# MCU.net
KiCad netlist of a schematic drawn in Altium Designer
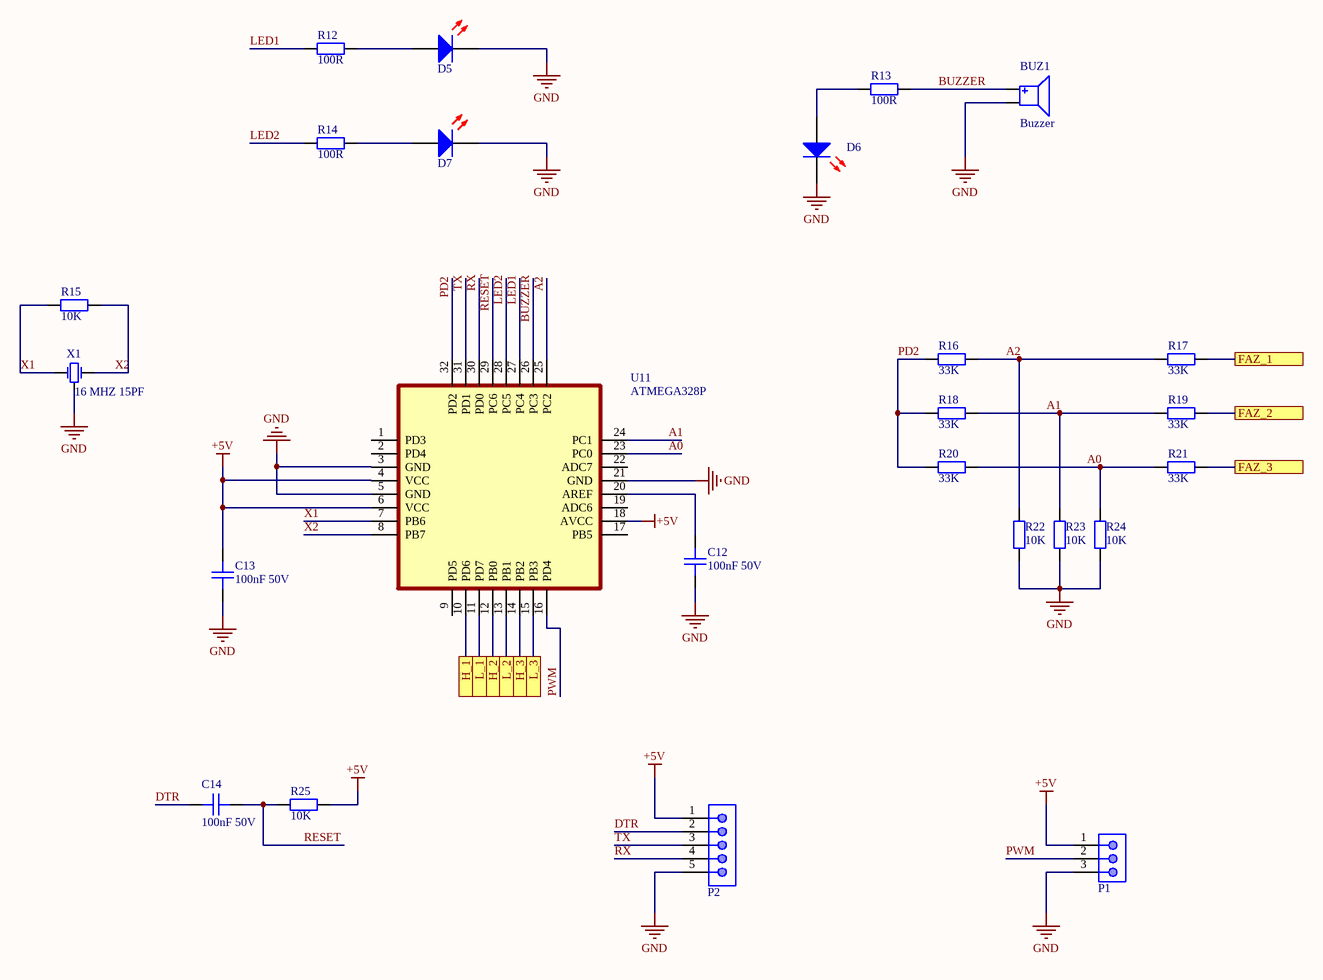
[diagram p0: MCU.SchDoc]

(export (version "E")
  (design (tool "Eeschema 10.0.6"))
  (components
    (comp (ref "BUZ1")
      (value "BUZZER MAGN 3.6V 7.5X7.5MM SMD")
      (footprint "BUZ: CMT-7525")
      (fields (field (name "DEGER") "Buzzer"))
      (libsource (lib "PROJE") (part "Buzzer(CMT-7525-80-SMT-TR)"))
    )
    (comp (ref "C12")
      (value "CAP CER 0.1UF 50V X7R 0805")
      (footprint "CAP 0805/2012")
      (description "0.1µF ±10% 50V Ceramic Capacitor X7R 0805 (2012 Metric)")
      (fields (field (name "DEGER") "100nF 50V"))
      (libsource (lib "PROJE") (part "100nF 50V 0805"))
    )
    (comp (ref "C13")
      (value "CAP CER 0.1UF 50V X7R 0805")
      (footprint "CAP 0805/2012")
      (description "0.1µF ±10% 50V Ceramic Capacitor X7R 0805 (2012 Metric)")
      (fields (field (name "DEGER") "100nF 50V"))
      (libsource (lib "PROJE") (part "100nF 50V 0805"))
    )
    (comp (ref "C14")
      (value "CAP CER 0.1UF 50V X7R 0805")
      (footprint "CAP 0805/2012")
      (description "0.1µF ±10% 50V Ceramic Capacitor X7R 0805 (2012 Metric)")
      (fields (field (name "DEGER") "100nF 50V"))
      (libsource (lib "PROJE") (part "100nF 50V 0805"))
    )
    (comp (ref "D5")
      (value "Red 645nm LED Indication - Discrete 1.8V 0805")
      (footprint "SMD: LED 0805/2012 RED")
      (description "LED RED DIFFUSED 0805 SMD")
      (libsource (lib "PROJE") (part "LED_Kırmızı"))
    )
    (comp (ref "D6")
      (value "Red 645nm LED Indication - Discrete 1.8V 0805")
      (footprint "SMD: LED 0805/2012 RED")
      (description "LED RED DIFFUSED 0805 SMD")
      (libsource (lib "PROJE") (part "LED_Kırmızı"))
    )
    (comp (ref "D7")
      (value "Red 645nm LED Indication - Discrete 1.8V 0805")
      (footprint "SMD: LED 0805/2012 RED")
      (description "LED RED DIFFUSED 0805 SMD")
      (libsource (lib "PROJE") (part "LED_Kırmızı"))
    )
    (comp (ref "P1")
      (value "WR-PHD 2.54 mm Angled Socket Header")
      (footprint "PWM_CONN")
      (libsource (lib "PROJE") (part "HDR(1X3)"))
    )
    (comp (ref "P2")
      (value "WR-PHD 2.54 mm Angled Socket Header")
      (footprint "TTL_CONN_5")
      (libsource (lib "PROJE") (part "HDR(1X5)"))
    )
    (comp (ref "R12")
      (value "RES SMD 100 OHM 1% 1/8W 0805")
      (footprint "RES_0805")
      (description "100 Ohms ±1% 0.125W, 1/8W Chip Resistor 0805 (2012 Metric) Moisture Resistant Thick Film")
      (fields (field (name "DEGER") "100R"))
      (libsource (lib "PROJE") (part "100R 0805"))
    )
    (comp (ref "R13")
      (value "RES SMD 100 OHM 1% 1/8W 0805")
      (footprint "RES_0805")
      (description "100 Ohms ±1% 0.125W, 1/8W Chip Resistor 0805 (2012 Metric) Moisture Resistant Thick Film")
      (fields (field (name "DEGER") "100R"))
      (libsource (lib "PROJE") (part "100R 0805"))
    )
    (comp (ref "R14")
      (value "RES SMD 100 OHM 1% 1/8W 0805")
      (footprint "RES_0805")
      (description "100 Ohms ±1% 0.125W, 1/8W Chip Resistor 0805 (2012 Metric) Moisture Resistant Thick Film")
      (fields (field (name "DEGER") "100R"))
      (libsource (lib "PROJE") (part "100R 0805"))
    )
    (comp (ref "R15")
      (value "RES SMD 10K OHM 1% 1/8W 0805")
      (footprint "RES_0805")
      (description "10 kOhms ±1% 0.125W, 1/8W Chip Resistor 0805 (2012 Metric) Moisture Resistant Thick Film")
      (fields (field (name "DEGER") "10K"))
      (libsource (lib "") (part "10K 0805_1"))
    )
    (comp (ref "R16")
      (value "RES SMD 33K OHM 1% 1/8W 0805")
      (footprint "RES_0805")
      (description "33 kOhms ±1% 0.125W, 1/8W Chip Resistor 0805 (2012 Metric) Moisture Resistant Thick Film")
      (fields (field (name "DEGER") "33K"))
      (libsource (lib "PROJE") (part "33K 0805"))
    )
    (comp (ref "R17")
      (value "RES SMD 33K OHM 1% 1/8W 0805")
      (footprint "RES_0805")
      (description "33 kOhms ±1% 0.125W, 1/8W Chip Resistor 0805 (2012 Metric) Moisture Resistant Thick Film")
      (fields (field (name "DEGER") "33K"))
      (libsource (lib "PROJE") (part "33K 0805"))
    )
    (comp (ref "R18")
      (value "RES SMD 33K OHM 1% 1/8W 0805")
      (footprint "RES_0805")
      (description "33 kOhms ±1% 0.125W, 1/8W Chip Resistor 0805 (2012 Metric) Moisture Resistant Thick Film")
      (fields (field (name "DEGER") "33K"))
      (libsource (lib "PROJE") (part "33K 0805"))
    )
    (comp (ref "R19")
      (value "RES SMD 33K OHM 1% 1/8W 0805")
      (footprint "RES_0805")
      (description "33 kOhms ±1% 0.125W, 1/8W Chip Resistor 0805 (2012 Metric) Moisture Resistant Thick Film")
      (fields (field (name "DEGER") "33K"))
      (libsource (lib "PROJE") (part "33K 0805"))
    )
    (comp (ref "R20")
      (value "RES SMD 33K OHM 1% 1/8W 0805")
      (footprint "RES_0805")
      (description "33 kOhms ±1% 0.125W, 1/8W Chip Resistor 0805 (2012 Metric) Moisture Resistant Thick Film")
      (fields (field (name "DEGER") "33K"))
      (libsource (lib "PROJE") (part "33K 0805"))
    )
    (comp (ref "R21")
      (value "RES SMD 33K OHM 1% 1/8W 0805")
      (footprint "RES_0805")
      (description "33 kOhms ±1% 0.125W, 1/8W Chip Resistor 0805 (2012 Metric) Moisture Resistant Thick Film")
      (fields (field (name "DEGER") "33K"))
      (libsource (lib "PROJE") (part "33K 0805"))
    )
    (comp (ref "R22")
      (value "RES SMD 10K OHM 1% 1/8W 0805")
      (footprint "RES_0805")
      (description "10 kOhms ±1% 0.125W, 1/8W Chip Resistor 0805 (2012 Metric) Moisture Resistant Thick Film")
      (fields (field (name "DEGER") "10K"))
      (libsource (lib "PROJE") (part "10K 0805"))
    )
    (comp (ref "R23")
      (value "RES SMD 10K OHM 1% 1/8W 0805")
      (footprint "RES_0805")
      (description "10 kOhms ±1% 0.125W, 1/8W Chip Resistor 0805 (2012 Metric) Moisture Resistant Thick Film")
      (fields (field (name "DEGER") "10K"))
      (libsource (lib "PROJE") (part "10K 0805"))
    )
    (comp (ref "R24")
      (value "RES SMD 10K OHM 1% 1/8W 0805")
      (footprint "RES_0805")
      (description "10 kOhms ±1% 0.125W, 1/8W Chip Resistor 0805 (2012 Metric) Moisture Resistant Thick Film")
      (fields (field (name "DEGER") "10K"))
      (libsource (lib "PROJE") (part "10K 0805"))
    )
    (comp (ref "R25")
      (value "RES SMD 10K OHM 1% 1/8W 0805")
      (footprint "RES_0805")
      (description "10 kOhms ±1% 0.125W, 1/8W Chip Resistor 0805 (2012 Metric) Moisture Resistant Thick Film")
      (fields (field (name "DEGER") "10K"))
      (libsource (lib "") (part "10K 0805_1"))
    )
    (comp (ref "U11")
      (value "IC MCU 8BIT 32KB FLASH 32TQFP")
      (footprint "TQFP32")
      (description "AVR AVR® ATmega Microcontroller IC 8-Bit 20MHz 32KB (16K x 16) FLASH 32-TQFP (7x7)")
      (fields (field (name "DEGER") "ATMEGA328P"))
      (libsource (lib "PROJE") (part "ATMEGA328P"))
    )
    (comp (ref "X1")
      (value "CERAMIC RES 16.0000MHZ 15PF SMD")
      (footprint "CRYSTAL_16MHZ(CTSE16)")
      (description "16MHz Ceramic Resonator Built in Capacitor 15pF ±0.3%  -20°C ~ 80°C Surface Mount")
      (fields (field (name "DEGER") "16 MHZ 15PF"))
      (libsource (lib "PROJE") (part "CRYSTAL 16.0000MHZ(CSTCE16M0V53-R0)"))
    )
  )
  (nets
    (net (code "1") (name "+5V") (class "Default")
      (node (ref "C13") (pin "2") (pinfunction "2_2") (pintype "passive"))
      (node (ref "P1") (pin "1") (pinfunction "1_1") (pintype "passive"))
      (node (ref "P2") (pin "1") (pinfunction "1_1") (pintype "passive"))
      (node (ref "R25") (pin "2") (pinfunction "2_2") (pintype "passive"))
      (node (ref "U11") (pin "18") (pinfunction "AVCC_18") (pintype "passive"))
      (node (ref "U11") (pin "4") (pinfunction "VCC_4") (pintype "passive"))
      (node (ref "U11") (pin "6") (pinfunction "VCC_6") (pintype "passive"))
    )
    (net (code "2") (name "/A0") (class "Default")
      (node (ref "R20") (pin "2") (pinfunction "2_2") (pintype "passive"))
      (node (ref "R21") (pin "1") (pinfunction "1_1") (pintype "passive"))
      (node (ref "R24") (pin "2") (pinfunction "2_2") (pintype "passive"))
      (node (ref "U11") (pin "23") (pinfunction "PC0_23") (pintype "passive"))
    )
    (net (code "3") (name "/A1") (class "Default")
      (node (ref "R18") (pin "2") (pinfunction "2_2") (pintype "passive"))
      (node (ref "R19") (pin "1") (pinfunction "1_1") (pintype "passive"))
      (node (ref "R23") (pin "2") (pinfunction "2_2") (pintype "passive"))
      (node (ref "U11") (pin "24") (pinfunction "PC1_24") (pintype "passive"))
    )
    (net (code "4") (name "/A2") (class "Default")
      (node (ref "R16") (pin "2") (pinfunction "2_2") (pintype "passive"))
      (node (ref "R17") (pin "1") (pinfunction "1_1") (pintype "passive"))
      (node (ref "R22") (pin "2") (pinfunction "2_2") (pintype "passive"))
      (node (ref "U11") (pin "25") (pinfunction "PC2_25") (pintype "passive"))
    )
    (net (code "5") (name "/BUZZER") (class "Default")
      (node (ref "BUZ1") (pin "1") (pinfunction "Positive_1") (pintype "passive"))
      (node (ref "R13") (pin "2") (pinfunction "2_2") (pintype "passive"))
      (node (ref "U11") (pin "26") (pinfunction "PC3_26") (pintype "passive"))
    )
    (net (code "6") (name "/DTR") (class "Default")
      (node (ref "C14") (pin "1") (pinfunction "1_1") (pintype "passive"))
      (node (ref "P2") (pin "2") (pinfunction "2_2") (pintype "passive"))
    )
    (net (code "7") (name "/FAZ_1") (class "Default")
      (node (ref "R17") (pin "2") (pinfunction "2_2") (pintype "passive"))
    )
    (net (code "8") (name "/FAZ_2") (class "Default")
      (node (ref "R19") (pin "2") (pinfunction "2_2") (pintype "passive"))
    )
    (net (code "9") (name "/FAZ_3") (class "Default")
      (node (ref "R21") (pin "2") (pinfunction "2_2") (pintype "passive"))
    )
    (net (code "10") (name "/H_1") (class "Default")
      (node (ref "U11") (pin "10") (pinfunction "PD6_10") (pintype "passive"))
    )
    (net (code "11") (name "/H_2") (class "Default")
      (node (ref "U11") (pin "12") (pinfunction "PB0_12") (pintype "passive"))
    )
    (net (code "12") (name "/H_3") (class "Default")
      (node (ref "U11") (pin "14") (pinfunction "PB2_14") (pintype "passive"))
    )
    (net (code "13") (name "/LED1") (class "Default")
      (node (ref "R12") (pin "1") (pinfunction "1_1") (pintype "passive"))
      (node (ref "U11") (pin "27") (pinfunction "PC4_27") (pintype "passive"))
    )
    (net (code "14") (name "/LED2") (class "Default")
      (node (ref "R14") (pin "1") (pinfunction "1_1") (pintype "passive"))
      (node (ref "U11") (pin "28") (pinfunction "PC5_28") (pintype "passive"))
    )
    (net (code "15") (name "/L_1") (class "Default")
      (node (ref "U11") (pin "11") (pinfunction "PD7_11") (pintype "passive"))
    )
    (net (code "16") (name "/L_2") (class "Default")
      (node (ref "U11") (pin "13") (pinfunction "PB1_13") (pintype "passive"))
    )
    (net (code "17") (name "/L_3") (class "Default")
      (node (ref "U11") (pin "15") (pinfunction "PB3_15") (pintype "passive"))
    )
    (net (code "18") (name "/PD2") (class "Default")
      (node (ref "R16") (pin "1") (pinfunction "1_1") (pintype "passive"))
      (node (ref "R18") (pin "1") (pinfunction "1_1") (pintype "passive"))
      (node (ref "R20") (pin "1") (pinfunction "1_1") (pintype "passive"))
      (node (ref "U11") (pin "32") (pinfunction "PD2_32") (pintype "passive"))
    )
    (net (code "19") (name "/PWM") (class "Default")
      (node (ref "P1") (pin "2") (pinfunction "2_2") (pintype "passive"))
      (node (ref "U11") (pin "16") (pinfunction "PD4_16") (pintype "passive"))
    )
    (net (code "20") (name "/RESET") (class "Default")
      (node (ref "C14") (pin "2") (pinfunction "2_2") (pintype "passive"))
      (node (ref "R25") (pin "1") (pinfunction "1_1") (pintype "passive"))
      (node (ref "U11") (pin "29") (pinfunction "PC6_29") (pintype "passive"))
    )
    (net (code "21") (name "/RX") (class "Default")
      (node (ref "P2") (pin "4") (pinfunction "4_4") (pintype "passive"))
      (node (ref "U11") (pin "30") (pinfunction "PD0_30") (pintype "passive"))
    )
    (net (code "22") (name "/TX") (class "Default")
      (node (ref "P2") (pin "3") (pinfunction "3_3") (pintype "passive"))
      (node (ref "U11") (pin "31") (pinfunction "PD1_31") (pintype "passive"))
    )
    (net (code "23") (name "/X1") (class "Default")
      (node (ref "R15") (pin "1") (pinfunction "1_1") (pintype "passive"))
      (node (ref "U11") (pin "7") (pinfunction "PB6_7") (pintype "passive"))
      (node (ref "X1") (pin "1") (pinfunction "OSC1_1") (pintype "passive"))
    )
    (net (code "24") (name "/X2") (class "Default")
      (node (ref "R15") (pin "2") (pinfunction "2_2") (pintype "passive"))
      (node (ref "U11") (pin "8") (pinfunction "PB7_8") (pintype "passive"))
      (node (ref "X1") (pin "3") (pinfunction "OSC2_3") (pintype "passive"))
    )
    (net (code "25") (name "GND") (class "Default")
      (node (ref "BUZ1") (pin "2") (pinfunction "Negative_2") (pintype "passive"))
      (node (ref "C12") (pin "1") (pinfunction "1_1") (pintype "passive"))
      (node (ref "C13") (pin "1") (pinfunction "1_1") (pintype "passive"))
      (node (ref "D5") (pin "2") (pinfunction "K_2") (pintype "passive"))
      (node (ref "D6") (pin "2") (pinfunction "K_2") (pintype "passive"))
      (node (ref "D7") (pin "2") (pinfunction "K_2") (pintype "passive"))
      (node (ref "P1") (pin "3") (pinfunction "3_3") (pintype "passive"))
      (node (ref "P2") (pin "5") (pinfunction "5_5") (pintype "passive"))
      (node (ref "R22") (pin "1") (pinfunction "1_1") (pintype "passive"))
      (node (ref "R23") (pin "1") (pinfunction "1_1") (pintype "passive"))
      (node (ref "R24") (pin "1") (pinfunction "1_1") (pintype "passive"))
      (node (ref "U11") (pin "21") (pinfunction "GND_21") (pintype "passive"))
      (node (ref "U11") (pin "3") (pinfunction "GND_3") (pintype "passive"))
      (node (ref "U11") (pin "5") (pinfunction "GND_5") (pintype "passive"))
      (node (ref "X1") (pin "2") (pinfunction "GND_2") (pintype "passive"))
    )
    (net (code "26") (name "Net-(D5-A)") (class "Default")
      (node (ref "D5") (pin "1") (pinfunction "A_1") (pintype "passive"))
      (node (ref "R12") (pin "2") (pinfunction "2_2") (pintype "passive"))
    )
    (net (code "27") (name "Net-(D6-A)") (class "Default")
      (node (ref "D6") (pin "1") (pinfunction "A_1") (pintype "passive"))
      (node (ref "R13") (pin "1") (pinfunction "1_1") (pintype "passive"))
    )
    (net (code "28") (name "Net-(D7-A)") (class "Default")
      (node (ref "D7") (pin "1") (pinfunction "A_1") (pintype "passive"))
      (node (ref "R14") (pin "2") (pinfunction "2_2") (pintype "passive"))
    )
    (net (code "29") (name "Net-(U11-AREF)") (class "Default")
      (node (ref "C12") (pin "2") (pinfunction "2_2") (pintype "passive"))
      (node (ref "U11") (pin "20") (pinfunction "AREF_20") (pintype "passive"))
    )
    (net (code "30") (name "unconnected-(U11-ADC6-Pad19)") (class "Default")
      (node (ref "U11") (pin "19") (pinfunction "ADC6_19") (pintype "passive"))
    )
    (net (code "31") (name "unconnected-(U11-ADC7-Pad22)") (class "Default")
      (node (ref "U11") (pin "22") (pinfunction "ADC7_22") (pintype "passive"))
    )
    (net (code "32") (name "unconnected-(U11-PB5-Pad17)") (class "Default")
      (node (ref "U11") (pin "17") (pinfunction "PB5_17") (pintype "passive"))
    )
    (net (code "33") (name "unconnected-(U11-PD3-Pad1)") (class "Default")
      (node (ref "U11") (pin "1") (pinfunction "PD3_1") (pintype "passive"))
    )
    (net (code "34") (name "unconnected-(U11-PD4-Pad2)") (class "Default")
      (node (ref "U11") (pin "2") (pinfunction "PD4_2") (pintype "passive"))
    )
    (net (code "35") (name "unconnected-(U11-PD5-Pad9)") (class "Default")
      (node (ref "U11") (pin "9") (pinfunction "PD5_9") (pintype "passive"))
    )
  )
)
